# 02_Connectors.net
KiCad netlist of a schematic drawn in Altium Designer
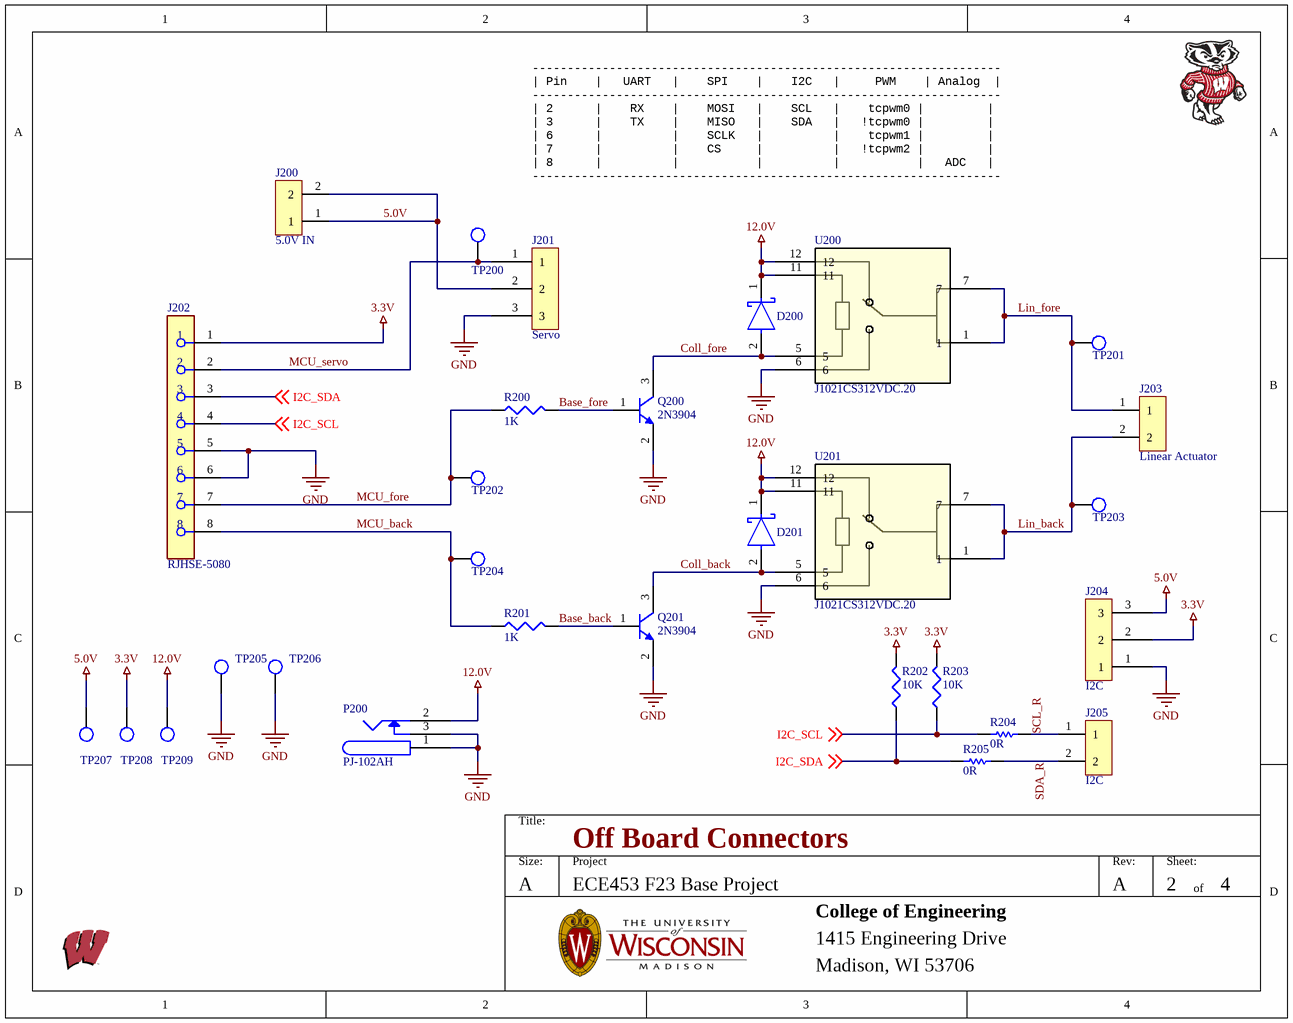
[diagram p0: 02_Connectors.SchDoc]

(export (version "E")
  (design (tool "Eeschema 10.0.6"))
  (components
    (comp (ref "D200")
      (value "SM5817PL-TP")
      (footprint "On_Semiconductor_425-04_IPC_A")
      (description "DIODE SCHOTTKY 20V 1A SOD123FL")
      (libsource (lib "ECE453") (part "SM5817PL-TP"))
    )
    (comp (ref "D201")
      (value "SM5817PL-TP")
      (footprint "On_Semiconductor_425-04_IPC_A")
      (description "DIODE SCHOTTKY 20V 1A SOD123FL")
      (libsource (lib "ECE453") (part "SM5817PL-TP"))
    )
    (comp (ref "J200")
      (value "5.0V IN")
      (footprint "PHOENIX2X0.2")
      (description "2~24 Poles, Screw Type, Horizontal, 5.08 Pitch, 26~14 (AWG), Terminal Block Connector")
      (fields
        (field (name "MANUFACTURER") "CUI Devices")
        (field (name "MANUFACTURER PART NUMBER") "TB006-508-02BE")
      )
      (libsource (lib "ECE453") (part "2-Pin"))
    )
    (comp (ref "J201")
      (value "Servo")
      (footprint "PHOENIX3X0.2")
      (description "2~24 Poles, Screw Type, Horizontal, 5.08 Pitch, 26~14 (AWG), Terminal Block Connector")
      (fields
        (field (name "MANUFACTURER") "CUI Devices")
        (field (name "MANUFACTURER PART NUMBER") "TB006-508-03BE")
      )
      (libsource (lib "") (part "3-Pin_2_1"))
    )
    (comp (ref "J202")
      (value "RJHSE-5080")
      (footprint "FP-RJHSE-5080-MFG")
      (description "CONN MOD JACK 8P8C R/A UNSHLD")
      (fields
        (field (name "OCTOPART") "https://octopart.com/rjhse-5080-amphenol-45060")
        (field (name "MANUFACTURER") "Amphenol")
      )
      (libsource (lib "Altium Content Vault") (part "b0a0b555dd3abf3683e7c330df25cc4"))
    )
    (comp (ref "J203")
      (value "Linear Actuator")
      (footprint "PHOENIX2X0.2")
      (description "2~24 Poles, Screw Type, Horizontal, 5.08 Pitch, 26~14 (AWG), Terminal Block Connector")
      (fields
        (field (name "MANUFACTURER") "CUI Devices")
        (field (name "MANUFACTURER PART NUMBER") "TB006-508-02BE")
      )
      (libsource (lib "") (part "2-Pin_1"))
    )
    (comp (ref "J204")
      (value "I2C")
      (footprint "PHOENIX3X0.2")
      (description "2~24 Poles, Screw Type, Horizontal, 5.08 Pitch, 26~14 (AWG), Terminal Block Connector")
      (fields
        (field (name "MANUFACTURER") "CUI Devices")
        (field (name "MANUFACTURER PART NUMBER") "TB006-508-03BE")
      )
      (libsource (lib "ECE453") (part "3-Pin_2"))
    )
    (comp (ref "J205")
      (value "I2C")
      (footprint "PHOENIX2X0.2")
      (description "2~24 Poles, Screw Type, Horizontal, 5.08 Pitch, 26~14 (AWG), Terminal Block Connector")
      (fields
        (field (name "MANUFACTURER") "CUI Devices")
        (field (name "MANUFACTURER PART NUMBER") "TB006-508-02BE")
      )
      (libsource (lib "") (part "2-Pin_1"))
    )
    (comp (ref "P200")
      (value "PJ-102")
      (footprint "PJ-102")
      (description "CONN PWR JACK 2.1X5.5MM HIGH CUR")
      (fields (field (name "MANUFACTURER") "CUI Inc") (field (name "MANUFACTURER PART NUMBER") "PJ-102AH"))
      (libsource (lib "ECE453") (part "CONN JACK PWR W/SW"))
    )
    (comp (ref "Q200")
      (value "2N3904")
      (footprint "SOT23-3M")
      (description "NPN General Purpose Amplifier")
      (fields
        (field (name "MANUFACTURER PART NUMBER") "MMBT3904-7-F")
        (field (name "MANUFACTURER") "Diodes Incorporated")
      )
      (libsource (lib "ECE453") (part "2N3904"))
    )
    (comp (ref "Q201")
      (value "2N3904")
      (footprint "SOT23-3M")
      (description "NPN General Purpose Amplifier")
      (fields
        (field (name "MANUFACTURER PART NUMBER") "MMBT3904-7-F")
        (field (name "MANUFACTURER") "Diodes Incorporated")
      )
      (libsource (lib "ECE453") (part "2N3904"))
    )
    (comp (ref "R200")
      (value "1K")
      (footprint "RESC2012M")
      (description "Res Thick Film 0805 1K Ohm 1% 0.125W(1/8W) ±100ppm/C Pad SMD Automotive T/R")
      (fields
        (field (name "MANUFACTURER") "Stackpole Electronics")
        (field (name "MANUFACTURER PART NUMBER") "RMCF0805FT1K00")
      )
      (libsource (lib "ECE453") (part "Res3_1"))
    )
    (comp (ref "R201")
      (value "1K")
      (footprint "RESC2012M")
      (description "Res Thick Film 0805 1K Ohm 1% 0.125W(1/8W) ±100ppm/C Pad SMD Automotive T/R")
      (fields
        (field (name "MANUFACTURER") "Stackpole Electronics")
        (field (name "MANUFACTURER PART NUMBER") "RMCF0805FT1K00")
      )
      (libsource (lib "ECE453") (part "Res3_1"))
    )
    (comp (ref "R202")
      (value "10K")
      (footprint "RESC2012M")
      (description "Res Thick Film 0805 10K Ohm 1% 0.125W ±100ppm/°C Molded SMD Paper T/R")
      (fields
        (field (name "MANUFACTURER") "Stackpole Electronics")
        (field (name "MANUFACTURER PART NUMBER") "RMCF0805FT10K0")
      )
      (libsource (lib "ECE453") (part "Res3"))
    )
    (comp (ref "R203")
      (value "10K")
      (footprint "RESC2012M")
      (description "Res Thick Film 0805 10K Ohm 1% 0.125W ±100ppm/°C Molded SMD Paper T/R")
      (fields
        (field (name "MANUFACTURER") "Stackpole Electronics")
        (field (name "MANUFACTURER PART NUMBER") "RMCF0805FT10K0")
      )
      (libsource (lib "ECE453") (part "Res3"))
    )
    (comp (ref "R204")
      (value "0R")
      (footprint "RESC2013X70X40NL20T20")
      (description "Chip Resistor, 0 Ohm, +/- 1%, 0.125 W, -55 to 155 degC, 0805 (2012 Metric), RoHS, Tape and Reel")
      (fields (field (name "PARTNUMBER") "ERJ-6GEY0R00V") (field (name "TOLERANCE") "5%"))
      (libsource (lib "ECE453") (part "CMP-1665-00002-5"))
    )
    (comp (ref "R205")
      (value "0R")
      (footprint "RESC2013X70X40NL20T20")
      (description "Chip Resistor, 0 Ohm, +/- 1%, 0.125 W, -55 to 155 degC, 0805 (2012 Metric), RoHS, Tape and Reel")
      (fields (field (name "PARTNUMBER") "ERJ-6GEY0R00V") (field (name "TOLERANCE") "5%"))
      (libsource (lib "ECE453") (part "CMP-1665-00002-5"))
    )
    (comp (ref "TP200")
      (value "TP_1206")
      (footprint "TP-SMC-1206")
      (description "Test Point SMD 1206")
      (fields
        (field (name "MANUFACTURER") "TE Connectivity (Tyco Electronics)")
        (field (name "MANUFACTURER PART NUMBER") "1625854-1")
      )
      (libsource (lib "ECE453") (part "TP_1206"))
    )
    (comp (ref "TP201")
      (value "TP_1206")
      (footprint "TP-SMC-1206")
      (description "Test Point SMD 1206")
      (fields
        (field (name "MANUFACTURER") "TE Connectivity (Tyco Electronics)")
        (field (name "MANUFACTURER PART NUMBER") "1625854-1")
      )
      (libsource (lib "ECE453") (part "TP_1206"))
    )
    (comp (ref "TP202")
      (value "TP_1206")
      (footprint "TP-SMC-1206")
      (description "Test Point SMD 1206")
      (fields
        (field (name "MANUFACTURER") "TE Connectivity (Tyco Electronics)")
        (field (name "MANUFACTURER PART NUMBER") "1625854-1")
      )
      (libsource (lib "ECE453") (part "TP_1206"))
    )
    (comp (ref "TP203")
      (value "TP_1206")
      (footprint "TP-SMC-1206")
      (description "Test Point SMD 1206")
      (fields
        (field (name "MANUFACTURER") "TE Connectivity (Tyco Electronics)")
        (field (name "MANUFACTURER PART NUMBER") "1625854-1")
      )
      (libsource (lib "ECE453") (part "TP_1206"))
    )
    (comp (ref "TP204")
      (value "TP_1206")
      (footprint "TP-SMC-1206")
      (description "Test Point SMD 1206")
      (fields
        (field (name "MANUFACTURER") "TE Connectivity (Tyco Electronics)")
        (field (name "MANUFACTURER PART NUMBER") "1625854-1")
      )
      (libsource (lib "ECE453") (part "TP_1206"))
    )
    (comp (ref "TP205")
      (value "TP_1206")
      (footprint "TP-SMC-1206")
      (description "Test Point SMD 1206")
      (fields
        (field (name "MANUFACTURER") "TE Connectivity (Tyco Electronics)")
        (field (name "MANUFACTURER PART NUMBER") "1625854-1")
      )
      (libsource (lib "ECE453") (part "TP_1206"))
    )
    (comp (ref "TP206")
      (value "TP_1206")
      (footprint "TP-SMC-1206")
      (description "Test Point SMD 1206")
      (fields
        (field (name "MANUFACTURER") "TE Connectivity (Tyco Electronics)")
        (field (name "MANUFACTURER PART NUMBER") "1625854-1")
      )
      (libsource (lib "ECE453") (part "TP_1206"))
    )
    (comp (ref "TP207")
      (value "TP_1206")
      (footprint "TP-SMC-1206")
      (description "Test Point SMD 1206")
      (fields
        (field (name "MANUFACTURER") "TE Connectivity (Tyco Electronics)")
        (field (name "MANUFACTURER PART NUMBER") "1625854-1")
      )
      (libsource (lib "ECE453") (part "TP_1206"))
    )
    (comp (ref "TP208")
      (value "TP_1206")
      (footprint "TP-SMC-1206")
      (description "Test Point SMD 1206")
      (fields
        (field (name "MANUFACTURER") "TE Connectivity (Tyco Electronics)")
        (field (name "MANUFACTURER PART NUMBER") "1625854-1")
      )
      (libsource (lib "ECE453") (part "TP_1206"))
    )
    (comp (ref "TP209")
      (value "TP_1206")
      (footprint "TP-SMC-1206")
      (description "Test Point SMD 1206")
      (fields
        (field (name "MANUFACTURER") "TE Connectivity (Tyco Electronics)")
        (field (name "MANUFACTURER PART NUMBER") "1625854-1")
      )
      (libsource (lib "ECE453") (part "TP_1206"))
    )
    (comp (ref "U200")
      (value "J1021CS312VDC.20")
      (footprint "RELAY6_J1021CS312VDC.20_CRS")
      (description "No Description Available")
      (fields (field (name "COPYRIGHT") "Copyright (C) 2023 Ultra Librarian. All rights reserved."))
      (libsource (lib "J1021CS312VDCP20") (part "J1021CS312VDC.20"))
    )
    (comp (ref "U201")
      (value "J1021CS312VDC.20")
      (footprint "RELAY6_J1021CS312VDC.20_CRS")
      (description "No Description Available")
      (fields (field (name "COPYRIGHT") "Copyright (C) 2023 Ultra Librarian. All rights reserved."))
      (libsource (lib "J1021CS312VDCP20") (part "J1021CS312VDC.20"))
    )
  )
  (nets
    (net (code "1") (name "/Base_back") (class "Default")
      (node (ref "Q201") (pin "1") (pinfunction "B_1") (pintype "passive"))
      (node (ref "R201") (pin "2") (pinfunction "2_2") (pintype "passive"))
    )
    (net (code "2") (name "/Base_fore") (class "Default")
      (node (ref "Q200") (pin "1") (pinfunction "B_1") (pintype "passive"))
      (node (ref "R200") (pin "2") (pinfunction "2_2") (pintype "passive"))
    )
    (net (code "3") (name "/Coll_back") (class "Default")
      (node (ref "D201") (pin "2") (pinfunction "A_2") (pintype "passive"))
      (node (ref "Q201") (pin "3") (pinfunction "C_3") (pintype "passive"))
      (node (ref "U201") (pin "5") (pinfunction "5_5") (pintype "passive"))
    )
    (net (code "4") (name "/Coll_fore") (class "Default")
      (node (ref "D200") (pin "2") (pinfunction "A_2") (pintype "passive"))
      (node (ref "Q200") (pin "3") (pinfunction "C_3") (pintype "passive"))
      (node (ref "U200") (pin "5") (pinfunction "5_5") (pintype "passive"))
    )
    (net (code "5") (name "/Lin_back") (class "Default")
      (node (ref "J203") (pin "2") (pinfunction "2_2") (pintype "passive"))
      (node (ref "TP203") (pin "1") (pintype "passive"))
      (node (ref "U201") (pin "1") (pinfunction "1_1") (pintype "passive"))
      (node (ref "U201") (pin "7") (pinfunction "7_7") (pintype "passive"))
    )
    (net (code "6") (name "/Lin_fore") (class "Default")
      (node (ref "J203") (pin "1") (pinfunction "1_1") (pintype "passive"))
      (node (ref "TP201") (pin "1") (pintype "passive"))
      (node (ref "U200") (pin "1") (pinfunction "1_1") (pintype "passive"))
      (node (ref "U200") (pin "7") (pinfunction "7_7") (pintype "passive"))
    )
    (net (code "7") (name "/MCU_back") (class "Default")
      (node (ref "J202") (pin "8") (pinfunction "8_8") (pintype "passive"))
      (node (ref "R201") (pin "1") (pinfunction "1_1") (pintype "passive"))
      (node (ref "TP204") (pin "1") (pintype "passive"))
    )
    (net (code "8") (name "/MCU_fore") (class "Default")
      (node (ref "J202") (pin "7") (pinfunction "7_7") (pintype "passive"))
      (node (ref "R200") (pin "1") (pinfunction "1_1") (pintype "passive"))
      (node (ref "TP202") (pin "1") (pintype "passive"))
    )
    (net (code "9") (name "/MCU_servo") (class "Default")
      (node (ref "J201") (pin "1") (pinfunction "1_1") (pintype "passive"))
      (node (ref "J202") (pin "2") (pinfunction "2_2") (pintype "passive"))
      (node (ref "TP200") (pin "1") (pintype "passive"))
    )
    (net (code "10") (name "/SCL_R") (class "Default")
      (node (ref "J205") (pin "1") (pinfunction "1_1") (pintype "passive"))
      (node (ref "R204") (pin "2") (pinfunction "2_2") (pintype "passive"))
    )
    (net (code "11") (name "/SDA_R") (class "Default")
      (node (ref "J205") (pin "2") (pinfunction "2_2") (pintype "passive"))
      (node (ref "R205") (pin "2") (pinfunction "2_2") (pintype "passive"))
    )
    (net (code "12") (name "3.3V") (class "Default")
      (node (ref "J202") (pin "1") (pinfunction "1_1") (pintype "passive"))
      (node (ref "J204") (pin "2") (pinfunction "2_2") (pintype "passive"))
      (node (ref "R202") (pin "2") (pinfunction "2_2") (pintype "passive"))
      (node (ref "R203") (pin "2") (pinfunction "2_2") (pintype "passive"))
      (node (ref "TP208") (pin "1") (pintype "passive"))
    )
    (net (code "13") (name "5.0V") (class "Default")
      (node (ref "J200") (pin "1") (pinfunction "1_1") (pintype "passive"))
      (node (ref "J200") (pin "2") (pinfunction "2_2") (pintype "passive"))
      (node (ref "J201") (pin "2") (pinfunction "2_2") (pintype "passive"))
      (node (ref "J204") (pin "3") (pinfunction "3_3") (pintype "passive"))
      (node (ref "TP207") (pin "1") (pintype "passive"))
    )
    (net (code "14") (name "12.0V") (class "Default")
      (node (ref "D200") (pin "1") (pinfunction "C_1") (pintype "passive"))
      (node (ref "D201") (pin "1") (pinfunction "C_1") (pintype "passive"))
      (node (ref "P200") (pin "2") (pinfunction "2_2") (pintype "passive"))
      (node (ref "TP209") (pin "1") (pintype "passive"))
      (node (ref "U200") (pin "11") (pinfunction "11_11") (pintype "passive"))
      (node (ref "U200") (pin "12") (pinfunction "12_12") (pintype "passive"))
      (node (ref "U201") (pin "11") (pinfunction "11_11") (pintype "passive"))
      (node (ref "U201") (pin "12") (pinfunction "12_12") (pintype "passive"))
    )
    (net (code "15") (name "GND") (class "Default")
      (node (ref "J201") (pin "3") (pinfunction "3_3") (pintype "passive"))
      (node (ref "J202") (pin "5") (pinfunction "5_5") (pintype "passive"))
      (node (ref "J202") (pin "6") (pinfunction "6_6") (pintype "passive"))
      (node (ref "J204") (pin "1") (pinfunction "1_1") (pintype "passive"))
      (node (ref "P200") (pin "1") (pinfunction "1_1") (pintype "passive"))
      (node (ref "P200") (pin "3") (pinfunction "3_3") (pintype "passive"))
      (node (ref "Q200") (pin "2") (pinfunction "E_2") (pintype "passive"))
      (node (ref "Q201") (pin "2") (pinfunction "E_2") (pintype "passive"))
      (node (ref "TP205") (pin "1") (pintype "passive"))
      (node (ref "TP206") (pin "1") (pintype "passive"))
      (node (ref "U200") (pin "6") (pinfunction "6_6") (pintype "passive"))
      (node (ref "U201") (pin "6") (pinfunction "6_6") (pintype "passive"))
    )
    (net (code "16") (name "I2C_SCL") (class "Default")
      (node (ref "J202") (pin "4") (pinfunction "4_4") (pintype "passive"))
      (node (ref "R203") (pin "1") (pinfunction "1_1") (pintype "passive"))
      (node (ref "R204") (pin "1") (pinfunction "1_1") (pintype "passive"))
    )
    (net (code "17") (name "I2C_SDA") (class "Default")
      (node (ref "J202") (pin "3") (pinfunction "3_3") (pintype "passive"))
      (node (ref "R202") (pin "1") (pinfunction "1_1") (pintype "passive"))
      (node (ref "R205") (pin "1") (pinfunction "1_1") (pintype "passive"))
    )
  )
)
